# ESP32_wroom_C.net
KiCad netlist of a schematic drawn in EasyEDA Pro
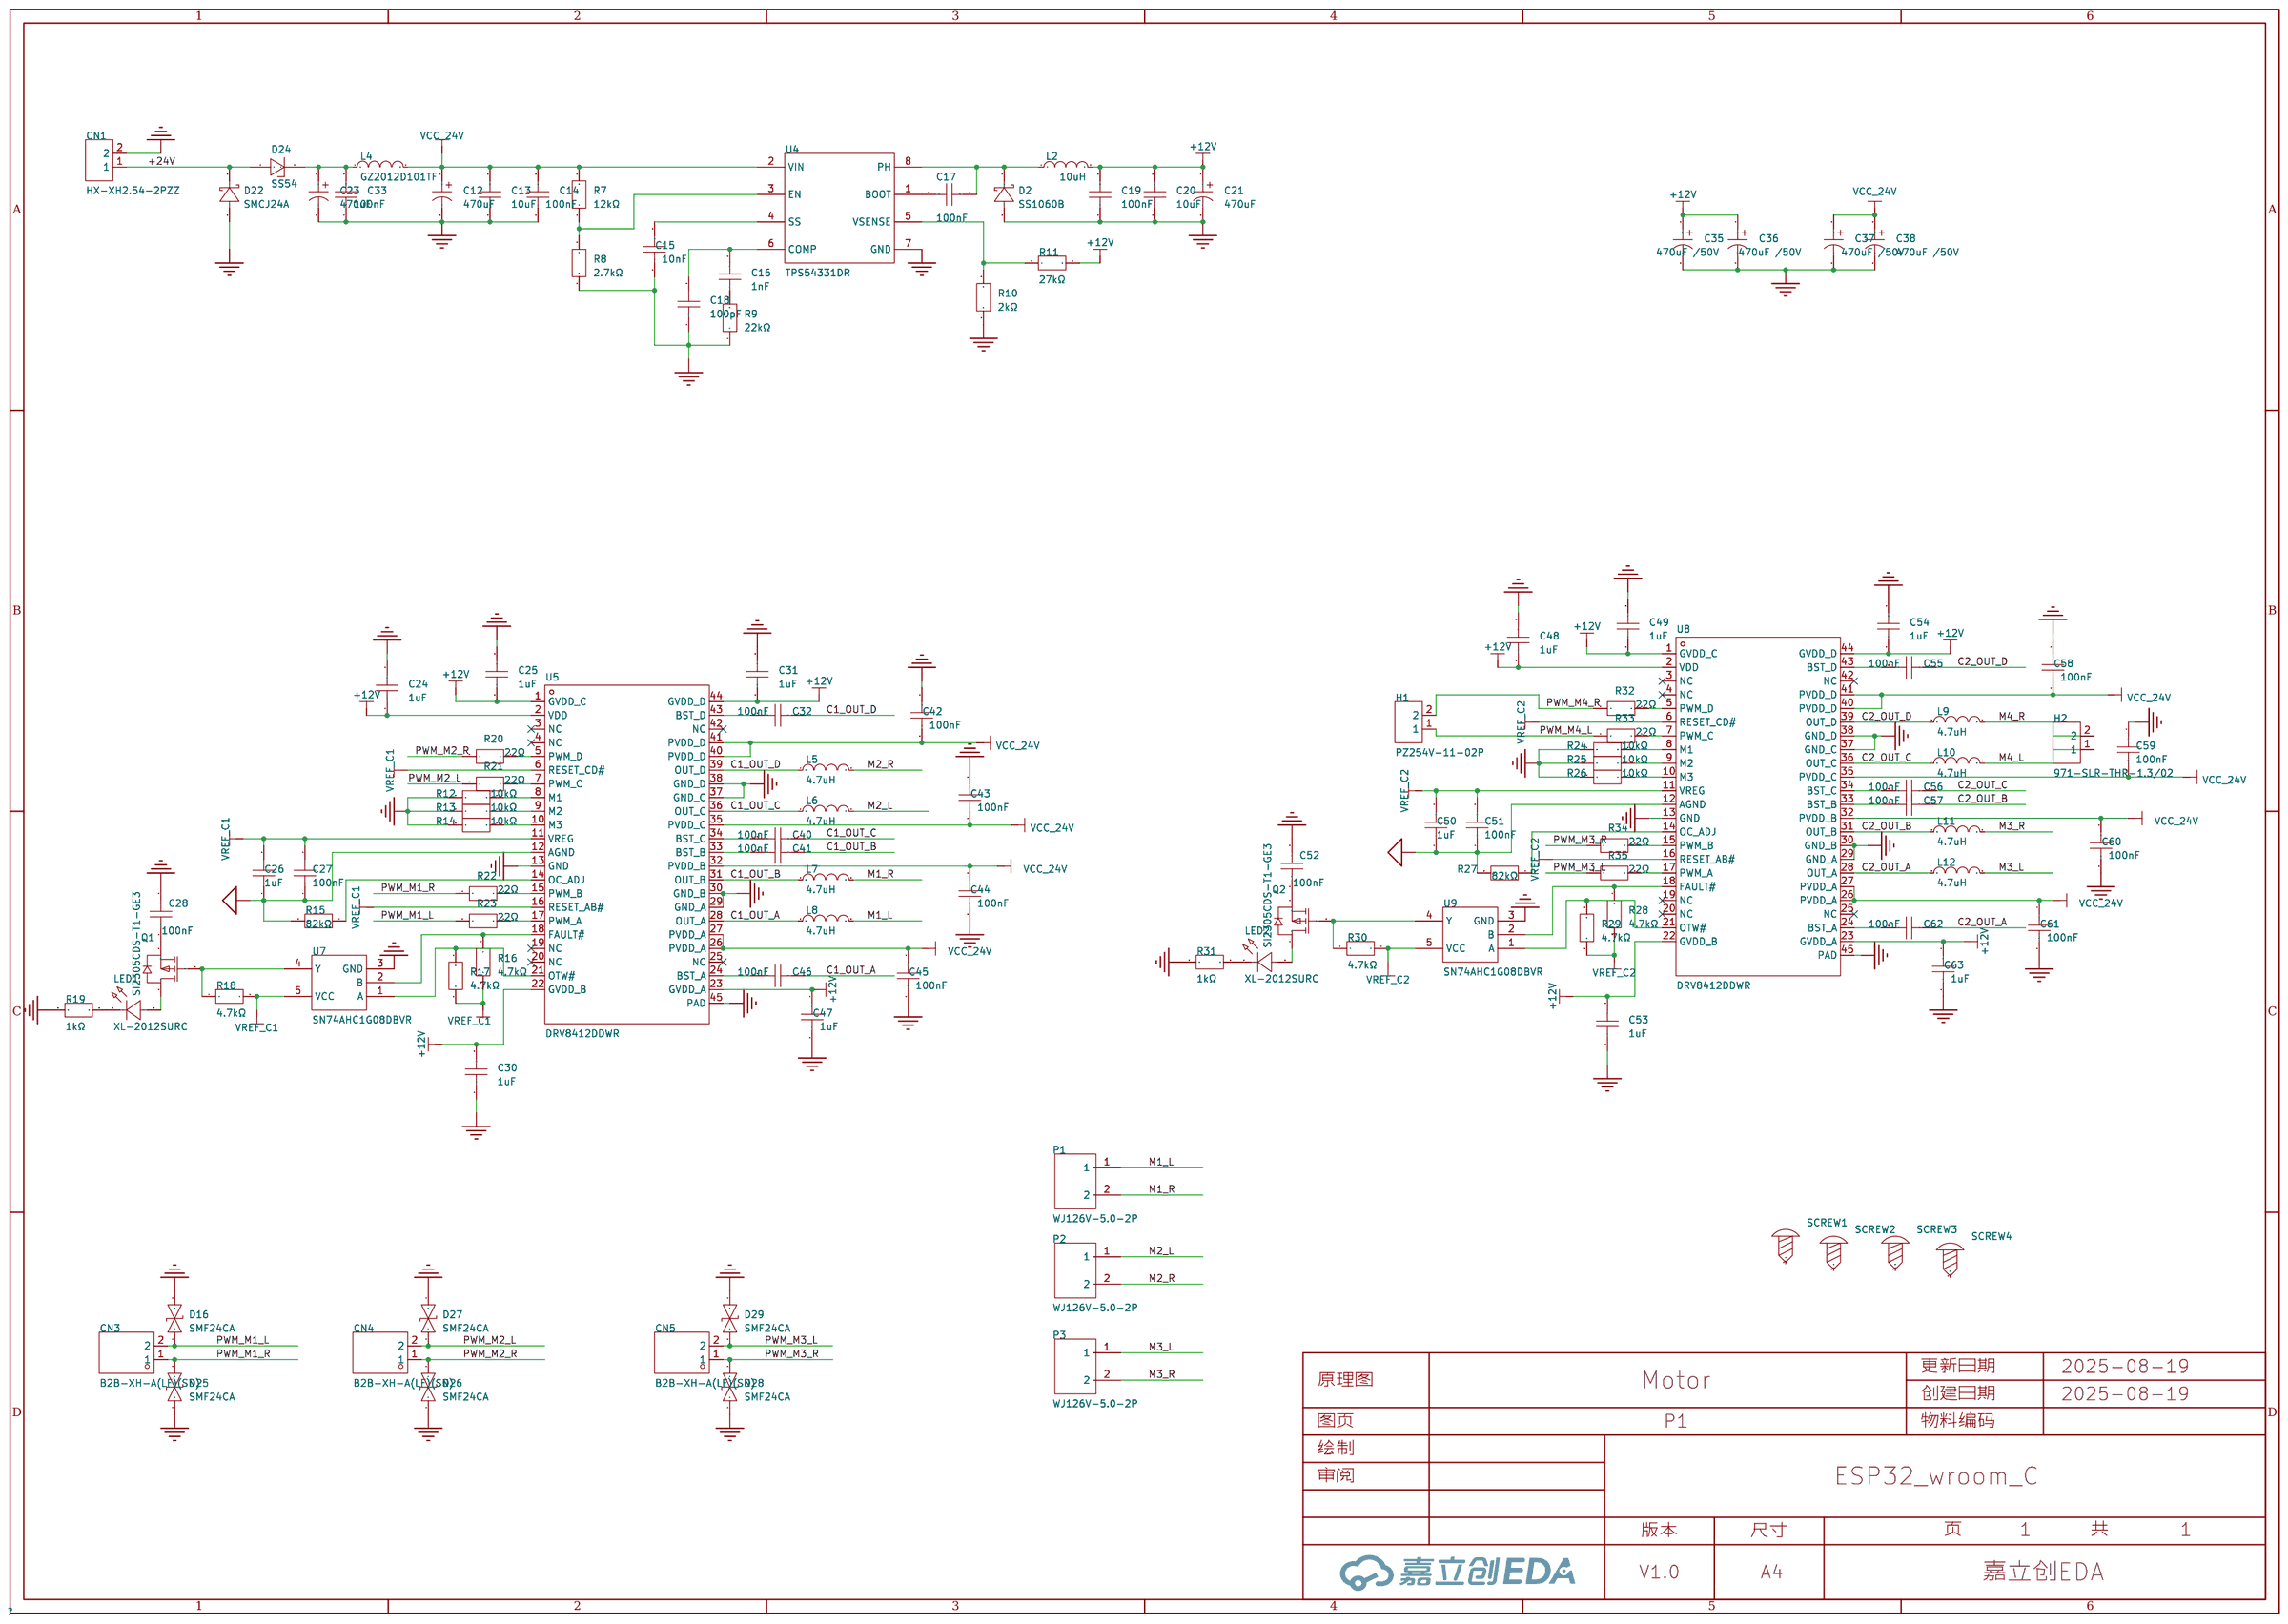
[diagram p0: schematic sheet]

(export (version "E")
  (design (tool "Eeschema 10.0.6"))
  (components
    (comp (ref "C12")
      (value "470uF")
      (footprint "easyedapro:CAP-TH_BD10.0-P5.00-D0.6-FD-A")
      (description "容值:470uF;精度:±20%;额定电压:50V;纹波电流:4.1A@100kHz;等效串联电阻(ESR):18mΩ@100kHz;类型:聚合物;")
      (fields (field (name "Manufacturer Part") "PA50V470M10x17") (field (name "Manufacturer") "捷而瑞"))
      (libsource (lib "easyedapro") (part "PA50V470M10X17"))
    )
    (comp (ref "C13")
      (value "10uF")
      (footprint "easyedapro:C0805")
      (description "容值:10uF;精度:±10%;额定电压:50V;材质(温度系数):X5R;")
      (fields
        (field (name "Manufacturer Part") "GRM21BR61H106KE43L")
        (field (name "Manufacturer") "muRata(村田)")
      )
      (libsource (lib "easyedapro") (part "GRM21BR61H106KE43L"))
    )
    (comp (ref "C14")
      (value "100nF")
      (footprint "easyedapro:C0603")
      (description "容值:100nF;精度:±10%;额定电压:50V;温度系数:X7R;")
      (fields
        (field (name "Manufacturer Part") "CGA0603X7R104K500JT")
        (field (name "Manufacturer") "HRE(芯声)")
      )
      (libsource (lib "easyedapro") (part "CGA0603X7R104K500JT"))
    )
    (comp (ref "C15")
      (value "10nF")
      (footprint "easyedapro:C0603")
      (description "容值:100nF;精度:±10%;额定电压:50V;温度系数:X7R;")
      (fields
        (field (name "Manufacturer Part") "CGA0603X7R104K500JT")
        (field (name "Manufacturer") "HRE(芯声)")
      )
      (libsource (lib "easyedapro") (part "CGA0603X7R104K500JT"))
    )
    (comp (ref "C16")
      (value "1nF")
      (footprint "easyedapro:C0603")
      (description "容值:100nF;精度:±10%;额定电压:50V;温度系数:X7R;")
      (fields
        (field (name "Manufacturer Part") "CGA0603X7R104K500JT")
        (field (name "Manufacturer") "HRE(芯声)")
      )
      (libsource (lib "easyedapro") (part "CGA0603X7R104K500JT"))
    )
    (comp (ref "C17")
      (value "100nF")
      (footprint "easyedapro:C0603")
      (description "容值:100nF;精度:±10%;额定电压:50V;温度系数:X7R;")
      (fields
        (field (name "Manufacturer Part") "CGA0603X7R104K500JT")
        (field (name "Manufacturer") "HRE(芯声)")
      )
      (libsource (lib "easyedapro") (part "CGA0603X7R104K500JT"))
    )
    (comp (ref "C18")
      (value "100pF")
      (footprint "easyedapro:C0603")
      (description "容值:100nF;精度:±10%;额定电压:50V;温度系数:X7R;")
      (fields
        (field (name "Manufacturer Part") "CGA0603X7R104K500JT")
        (field (name "Manufacturer") "HRE(芯声)")
      )
      (libsource (lib "easyedapro") (part "CGA0603X7R104K500JT"))
    )
    (comp (ref "C19")
      (value "100nF")
      (footprint "easyedapro:C0603")
      (description "容值:100nF;精度:±10%;额定电压:50V;温度系数:X7R;")
      (fields
        (field (name "Manufacturer Part") "CGA0603X7R104K500JT")
        (field (name "Manufacturer") "HRE(芯声)")
      )
      (libsource (lib "easyedapro") (part "CGA0603X7R104K500JT"))
    )
    (comp (ref "C20")
      (value "10uF")
      (footprint "easyedapro:C0805")
      (description "容值:10uF;精度:±10%;额定电压:50V;材质(温度系数):X5R;")
      (fields
        (field (name "Manufacturer Part") "GRM21BR61H106KE43L")
        (field (name "Manufacturer") "muRata(村田)")
      )
      (libsource (lib "easyedapro") (part "GRM21BR61H106KE43L"))
    )
    (comp (ref "C21")
      (value "470uF")
      (footprint "easyedapro:CAP-TH_BD10.0-P5.00-D0.6-FD-A")
      (description "容值:470uF;精度:±20%;额定电压:50V;纹波电流:4.1A@100kHz;等效串联电阻(ESR):18mΩ@100kHz;类型:聚合物;")
      (fields (field (name "Manufacturer Part") "PA50V470M10x17") (field (name "Manufacturer") "捷而瑞"))
      (libsource (lib "easyedapro") (part "PA50V470M10X17"))
    )
    (comp (ref "C23")
      (value "470uF")
      (footprint "easyedapro:CAP-TH_BD10.0-P5.00-D0.6-FD-A")
      (description "容值:470uF;精度:±20%;额定电压:50V;纹波电流:4.1A@100kHz;等效串联电阻(ESR):18mΩ@100kHz;类型:聚合物;")
      (fields (field (name "Manufacturer Part") "PA50V470M10x17") (field (name "Manufacturer") "捷而瑞"))
      (libsource (lib "easyedapro") (part "PA50V470M10X17"))
    )
    (comp (ref "C24")
      (value "1uF")
      (footprint "easyedapro:C0805")
      (description "容值:10uF;精度:±10%;额定电压:50V;材质(温度系数):X5R;")
      (fields
        (field (name "Manufacturer Part") "GRM21BR61H106KE43L")
        (field (name "Manufacturer") "muRata(村田)")
      )
      (libsource (lib "easyedapro") (part "GRM21BR61H106KE43L"))
    )
    (comp (ref "C25")
      (value "1uF")
      (footprint "easyedapro:C0805")
      (description "容值:10uF;精度:±10%;额定电压:50V;材质(温度系数):X5R;")
      (fields
        (field (name "Manufacturer Part") "GRM21BR61H106KE43L")
        (field (name "Manufacturer") "muRata(村田)")
      )
      (libsource (lib "easyedapro") (part "GRM21BR61H106KE43L"))
    )
    (comp (ref "C26")
      (value "1uF")
      (footprint "easyedapro:C0805")
      (description "容值:10uF;精度:±10%;额定电压:50V;材质(温度系数):X5R;")
      (fields
        (field (name "Manufacturer Part") "GRM21BR61H106KE43L")
        (field (name "Manufacturer") "muRata(村田)")
      )
      (libsource (lib "easyedapro") (part "GRM21BR61H106KE43L"))
    )
    (comp (ref "C27")
      (value "100nF")
      (footprint "easyedapro:C0805")
      (description "容值:10uF;精度:±10%;额定电压:50V;材质(温度系数):X5R;")
      (fields
        (field (name "Manufacturer Part") "GRM21BR61H106KE43L")
        (field (name "Manufacturer") "muRata(村田)")
      )
      (libsource (lib "easyedapro") (part "GRM21BR61H106KE43L"))
    )
    (comp (ref "C28")
      (value "100nF")
      (footprint "easyedapro:C0805")
      (description "容值:10uF;精度:±10%;额定电压:50V;材质(温度系数):X5R;")
      (fields
        (field (name "Manufacturer Part") "GRM21BR61H106KE43L")
        (field (name "Manufacturer") "muRata(村田)")
      )
      (libsource (lib "easyedapro") (part "GRM21BR61H106KE43L"))
    )
    (comp (ref "C30")
      (value "1uF")
      (footprint "easyedapro:C0805")
      (description "容值:10uF;精度:±10%;额定电压:50V;材质(温度系数):X5R;")
      (fields
        (field (name "Manufacturer Part") "GRM21BR61H106KE43L")
        (field (name "Manufacturer") "muRata(村田)")
      )
      (libsource (lib "easyedapro") (part "GRM21BR61H106KE43L"))
    )
    (comp (ref "C31")
      (value "1uF")
      (footprint "easyedapro:C0805")
      (description "容值:10uF;精度:±10%;额定电压:50V;材质(温度系数):X5R;")
      (fields
        (field (name "Manufacturer Part") "GRM21BR61H106KE43L")
        (field (name "Manufacturer") "muRata(村田)")
      )
      (libsource (lib "easyedapro") (part "GRM21BR61H106KE43L"))
    )
    (comp (ref "C32")
      (value "100nF")
      (footprint "easyedapro:C0805")
      (description "容值:10uF;精度:±10%;额定电压:50V;材质(温度系数):X5R;")
      (fields
        (field (name "Manufacturer Part") "GRM21BR61H106KE43L")
        (field (name "Manufacturer") "muRata(村田)")
      )
      (libsource (lib "easyedapro") (part "GRM21BR61H106KE43L"))
    )
    (comp (ref "C33")
      (value "100nF")
      (footprint "easyedapro:C0603")
      (description "容值:100nF;精度:±10%;额定电压:50V;温度系数:X7R;")
      (fields
        (field (name "Manufacturer Part") "CGA0603X7R104K500JT")
        (field (name "Manufacturer") "HRE(芯声)")
      )
      (libsource (lib "easyedapro") (part "CGA0603X7R104K500JT"))
    )
    (comp (ref "C35")
      (value "470uF /50V")
      (footprint "easyedapro:CAP-TH_BD10.0-P5.00-D0.6-FD-A")
      (description "容值:470uF;精度:±20%;额定电压:50V;纹波电流:4.1A@100kHz;等效串联电阻(ESR):18mΩ@100kHz;类型:聚合物;")
      (fields (field (name "Manufacturer Part") "PA50V470M10x17") (field (name "Manufacturer") "捷而瑞"))
      (libsource (lib "easyedapro") (part "PA50V470M10X17"))
    )
    (comp (ref "C36")
      (value "470uF /50V")
      (footprint "easyedapro:CAP-TH_BD10.0-P5.00-D0.6-FD-A")
      (description "容值:470uF;精度:±20%;额定电压:50V;纹波电流:4.1A@100kHz;等效串联电阻(ESR):18mΩ@100kHz;类型:聚合物;")
      (fields (field (name "Manufacturer Part") "PA50V470M10x17") (field (name "Manufacturer") "捷而瑞"))
      (libsource (lib "easyedapro") (part "PA50V470M10X17"))
    )
    (comp (ref "C37")
      (value "470uF /50V")
      (footprint "easyedapro:CAP-TH_BD10.0-P5.00-D0.6-FD-A")
      (description "容值:470uF;精度:±20%;额定电压:50V;纹波电流:4.1A@100kHz;等效串联电阻(ESR):18mΩ@100kHz;类型:聚合物;")
      (fields (field (name "Manufacturer Part") "PA50V470M10x17") (field (name "Manufacturer") "捷而瑞"))
      (libsource (lib "easyedapro") (part "PA50V470M10X17"))
    )
    (comp (ref "C38")
      (value "470uF /50V")
      (footprint "easyedapro:CAP-TH_BD10.0-P5.00-D0.6-FD-A")
      (description "容值:470uF;精度:±20%;额定电压:50V;纹波电流:4.1A@100kHz;等效串联电阻(ESR):18mΩ@100kHz;类型:聚合物;")
      (fields (field (name "Manufacturer Part") "PA50V470M10x17") (field (name "Manufacturer") "捷而瑞"))
      (libsource (lib "easyedapro") (part "PA50V470M10X17"))
    )
    (comp (ref "C40")
      (value "100nF")
      (footprint "easyedapro:C0805")
      (description "容值:10uF;精度:±10%;额定电压:50V;材质(温度系数):X5R;")
      (fields
        (field (name "Manufacturer Part") "GRM21BR61H106KE43L")
        (field (name "Manufacturer") "muRata(村田)")
      )
      (libsource (lib "easyedapro") (part "GRM21BR61H106KE43L"))
    )
    (comp (ref "C41")
      (value "100nF")
      (footprint "easyedapro:C0805")
      (description "容值:10uF;精度:±10%;额定电压:50V;材质(温度系数):X5R;")
      (fields
        (field (name "Manufacturer Part") "GRM21BR61H106KE43L")
        (field (name "Manufacturer") "muRata(村田)")
      )
      (libsource (lib "easyedapro") (part "GRM21BR61H106KE43L"))
    )
    (comp (ref "C42")
      (value "100nF")
      (footprint "easyedapro:C0805")
      (description "容值:10uF;精度:±10%;额定电压:50V;材质(温度系数):X5R;")
      (fields
        (field (name "Manufacturer Part") "GRM21BR61H106KE43L")
        (field (name "Manufacturer") "muRata(村田)")
      )
      (libsource (lib "easyedapro") (part "GRM21BR61H106KE43L"))
    )
    (comp (ref "C43")
      (value "100nF")
      (footprint "easyedapro:C0805")
      (description "容值:10uF;精度:±10%;额定电压:50V;材质(温度系数):X5R;")
      (fields
        (field (name "Manufacturer Part") "GRM21BR61H106KE43L")
        (field (name "Manufacturer") "muRata(村田)")
      )
      (libsource (lib "easyedapro") (part "GRM21BR61H106KE43L"))
    )
    (comp (ref "C44")
      (value "100nF")
      (footprint "easyedapro:C0805")
      (description "容值:10uF;精度:±10%;额定电压:50V;材质(温度系数):X5R;")
      (fields
        (field (name "Manufacturer Part") "GRM21BR61H106KE43L")
        (field (name "Manufacturer") "muRata(村田)")
      )
      (libsource (lib "easyedapro") (part "GRM21BR61H106KE43L"))
    )
    (comp (ref "C45")
      (value "100nF")
      (footprint "easyedapro:C0805")
      (description "容值:10uF;精度:±10%;额定电压:50V;材质(温度系数):X5R;")
      (fields
        (field (name "Manufacturer Part") "GRM21BR61H106KE43L")
        (field (name "Manufacturer") "muRata(村田)")
      )
      (libsource (lib "easyedapro") (part "GRM21BR61H106KE43L"))
    )
    (comp (ref "C46")
      (value "100nF")
      (footprint "easyedapro:C0805")
      (description "容值:10uF;精度:±10%;额定电压:50V;材质(温度系数):X5R;")
      (fields
        (field (name "Manufacturer Part") "GRM21BR61H106KE43L")
        (field (name "Manufacturer") "muRata(村田)")
      )
      (libsource (lib "easyedapro") (part "GRM21BR61H106KE43L"))
    )
    (comp (ref "C47")
      (value "1uF")
      (footprint "easyedapro:C0805")
      (description "容值:10uF;精度:±10%;额定电压:50V;材质(温度系数):X5R;")
      (fields
        (field (name "Manufacturer Part") "GRM21BR61H106KE43L")
        (field (name "Manufacturer") "muRata(村田)")
      )
      (libsource (lib "easyedapro") (part "GRM21BR61H106KE43L"))
    )
    (comp (ref "C48")
      (value "1uF")
      (footprint "easyedapro:C0805")
      (description "容值:10uF;精度:±10%;额定电压:50V;材质(温度系数):X5R;")
      (fields
        (field (name "Manufacturer Part") "GRM21BR61H106KE43L")
        (field (name "Manufacturer") "muRata(村田)")
      )
      (libsource (lib "easyedapro") (part "GRM21BR61H106KE43L"))
    )
    (comp (ref "C49")
      (value "1uF")
      (footprint "easyedapro:C0805")
      (description "容值:10uF;精度:±10%;额定电压:50V;材质(温度系数):X5R;")
      (fields
        (field (name "Manufacturer Part") "GRM21BR61H106KE43L")
        (field (name "Manufacturer") "muRata(村田)")
      )
      (libsource (lib "easyedapro") (part "GRM21BR61H106KE43L"))
    )
    (comp (ref "C50")
      (value "1uF")
      (footprint "easyedapro:C0805")
      (description "容值:10uF;精度:±10%;额定电压:50V;材质(温度系数):X5R;")
      (fields
        (field (name "Manufacturer Part") "GRM21BR61H106KE43L")
        (field (name "Manufacturer") "muRata(村田)")
      )
      (libsource (lib "easyedapro") (part "GRM21BR61H106KE43L"))
    )
    (comp (ref "C51")
      (value "100nF")
      (footprint "easyedapro:C0805")
      (description "容值:10uF;精度:±10%;额定电压:50V;材质(温度系数):X5R;")
      (fields
        (field (name "Manufacturer Part") "GRM21BR61H106KE43L")
        (field (name "Manufacturer") "muRata(村田)")
      )
      (libsource (lib "easyedapro") (part "GRM21BR61H106KE43L"))
    )
    (comp (ref "C52")
      (value "100nF")
      (footprint "easyedapro:C0805")
      (description "容值:10uF;精度:±10%;额定电压:50V;材质(温度系数):X5R;")
      (fields
        (field (name "Manufacturer Part") "GRM21BR61H106KE43L")
        (field (name "Manufacturer") "muRata(村田)")
      )
      (libsource (lib "easyedapro") (part "GRM21BR61H106KE43L"))
    )
    (comp (ref "C53")
      (value "1uF")
      (footprint "easyedapro:C0805")
      (description "容值:10uF;精度:±10%;额定电压:50V;材质(温度系数):X5R;")
      (fields
        (field (name "Manufacturer Part") "GRM21BR61H106KE43L")
        (field (name "Manufacturer") "muRata(村田)")
      )
      (libsource (lib "easyedapro") (part "GRM21BR61H106KE43L"))
    )
    (comp (ref "C54")
      (value "1uF")
      (footprint "easyedapro:C0805")
      (description "容值:10uF;精度:±10%;额定电压:50V;材质(温度系数):X5R;")
      (fields
        (field (name "Manufacturer Part") "GRM21BR61H106KE43L")
        (field (name "Manufacturer") "muRata(村田)")
      )
      (libsource (lib "easyedapro") (part "GRM21BR61H106KE43L"))
    )
    (comp (ref "C55")
      (value "100nF")
      (footprint "easyedapro:C0805")
      (description "容值:10uF;精度:±10%;额定电压:50V;材质(温度系数):X5R;")
      (fields
        (field (name "Manufacturer Part") "GRM21BR61H106KE43L")
        (field (name "Manufacturer") "muRata(村田)")
      )
      (libsource (lib "easyedapro") (part "GRM21BR61H106KE43L"))
    )
    (comp (ref "C56")
      (value "100nF")
      (footprint "easyedapro:C0805")
      (description "容值:10uF;精度:±10%;额定电压:50V;材质(温度系数):X5R;")
      (fields
        (field (name "Manufacturer Part") "GRM21BR61H106KE43L")
        (field (name "Manufacturer") "muRata(村田)")
      )
      (libsource (lib "easyedapro") (part "GRM21BR61H106KE43L"))
    )
    (comp (ref "C57")
      (value "100nF")
      (footprint "easyedapro:C0805")
      (description "容值:10uF;精度:±10%;额定电压:50V;材质(温度系数):X5R;")
      (fields
        (field (name "Manufacturer Part") "GRM21BR61H106KE43L")
        (field (name "Manufacturer") "muRata(村田)")
      )
      (libsource (lib "easyedapro") (part "GRM21BR61H106KE43L"))
    )
    (comp (ref "C58")
      (value "100nF")
      (footprint "easyedapro:C0805")
      (description "容值:10uF;精度:±10%;额定电压:50V;材质(温度系数):X5R;")
      (fields
        (field (name "Manufacturer Part") "GRM21BR61H106KE43L")
        (field (name "Manufacturer") "muRata(村田)")
      )
      (libsource (lib "easyedapro") (part "GRM21BR61H106KE43L"))
    )
    (comp (ref "C59")
      (value "100nF")
      (footprint "easyedapro:C0805")
      (description "容值:10uF;精度:±10%;额定电压:50V;材质(温度系数):X5R;")
      (fields
        (field (name "Manufacturer Part") "GRM21BR61H106KE43L")
        (field (name "Manufacturer") "muRata(村田)")
      )
      (libsource (lib "easyedapro") (part "GRM21BR61H106KE43L"))
    )
    (comp (ref "C60")
      (value "100nF")
      (footprint "easyedapro:C0805")
      (description "容值:10uF;精度:±10%;额定电压:50V;材质(温度系数):X5R;")
      (fields
        (field (name "Manufacturer Part") "GRM21BR61H106KE43L")
        (field (name "Manufacturer") "muRata(村田)")
      )
      (libsource (lib "easyedapro") (part "GRM21BR61H106KE43L"))
    )
    (comp (ref "C61")
      (value "100nF")
      (footprint "easyedapro:C0805")
      (description "容值:10uF;精度:±10%;额定电压:50V;材质(温度系数):X5R;")
      (fields
        (field (name "Manufacturer Part") "GRM21BR61H106KE43L")
        (field (name "Manufacturer") "muRata(村田)")
      )
      (libsource (lib "easyedapro") (part "GRM21BR61H106KE43L"))
    )
    (comp (ref "C62")
      (value "100nF")
      (footprint "easyedapro:C0805")
      (description "容值:10uF;精度:±10%;额定电压:50V;材质(温度系数):X5R;")
      (fields
        (field (name "Manufacturer Part") "GRM21BR61H106KE43L")
        (field (name "Manufacturer") "muRata(村田)")
      )
      (libsource (lib "easyedapro") (part "GRM21BR61H106KE43L"))
    )
    (comp (ref "C63")
      (value "1uF")
      (footprint "easyedapro:C0805")
      (description "容值:10uF;精度:±10%;额定电压:50V;材质(温度系数):X5R;")
      (fields
        (field (name "Manufacturer Part") "GRM21BR61H106KE43L")
        (field (name "Manufacturer") "muRata(村田)")
      )
      (libsource (lib "easyedapro") (part "GRM21BR61H106KE43L"))
    )
    (comp (ref "CN1")
      (value "HX-XH2.54-2PZZ")
      (footprint "easyedapro:CONN-TH_2P-P2.50_HX-2.54MM-2P-ZZ-MS")
      (fields (field (name "Manufacturer") "hanxia(韩下)"))
      (libsource (lib "easyedapro") (part "HX-XH2.54-2PZZ"))
    )
    (comp (ref "CN3")
      (value "B2B-XH-A(LF)(SN)")
      (footprint "easyedapro:CONN-TH_B2B-XH-A-LF-SN")
      (fields (field (name "Manufacturer") "JST"))
      (libsource (lib "easyedapro") (part "B2B-XH-A (LF)(SN)"))
    )
    (comp (ref "CN4")
      (value "B2B-XH-A(LF)(SN)")
      (footprint "easyedapro:CONN-TH_B2B-XH-A-LF-SN")
      (fields (field (name "Manufacturer") "JST"))
      (libsource (lib "easyedapro") (part "B2B-XH-A (LF)(SN)"))
    )
    (comp (ref "CN5")
      (value "B2B-XH-A(LF)(SN)")
      (footprint "easyedapro:CONN-TH_B2B-XH-A-LF-SN")
      (fields (field (name "Manufacturer") "JST"))
      (libsource (lib "easyedapro") (part "B2B-XH-A (LF)(SN)"))
    )
    (comp (ref "D2")
      (value "SS1060B")
      (footprint "easyedapro:SMB_L4.3-W3.6-LS5.3-RD")
      (description "正向压降(Vf):700mV@10A;直流反向耐压(Vr):60V;整流电流:10A;")
      (fields (field (name "Manufacturer") "Slkor(萨科微)"))
      (libsource (lib "easyedapro") (part "SS1060B_C18208635"))
    )
    (comp (ref "D16")
      (value "SMF24CA")
      (footprint "easyedapro:SOD-123FL_L2.7-W1.8-LS3.8-BI")
      (fields (field (name "Manufacturer") "宏迦橙"))
      (libsource (lib "easyedapro") (part "SMF24CA_C19077515"))
    )
    (comp (ref "D22")
      (value "SMCJ24A")
      (footprint "easyedapro:SMC_L6.9-W5.9-LS7.9-RD")
      (fields (field (name "Manufacturer") "宏嘉诚"))
      (libsource (lib "easyedapro") (part "SMCJ24A_C19077604"))
    )
    (comp (ref "D24")
      (value "SS54")
      (footprint "easyedapro:SMA_L4.3-W2.6-LS5.0-FD")
      (description "二极管配置:独立式;正向压降(Vf):550mV@5.0A;直流反向耐压(Vr):40V;整流电流:5A;")
      (fields (field (name "Manufacturer") "宏嘉诚"))
      (libsource (lib "easyedapro") (part "SS54_C7420369"))
    )
    (comp (ref "D25")
      (value "SMF24CA")
      (footprint "easyedapro:SOD-123FL_L2.7-W1.8-LS3.8-BI")
      (fields (field (name "Manufacturer") "宏迦橙"))
      (libsource (lib "easyedapro") (part "SMF24CA_C19077515"))
    )
    (comp (ref "D26")
      (value "SMF24CA")
      (footprint "easyedapro:SOD-123FL_L2.7-W1.8-LS3.8-BI")
      (fields (field (name "Manufacturer") "宏迦橙"))
      (libsource (lib "easyedapro") (part "SMF24CA_C19077515"))
    )
    (comp (ref "D27")
      (value "SMF24CA")
      (footprint "easyedapro:SOD-123FL_L2.7-W1.8-LS3.8-BI")
      (fields (field (name "Manufacturer") "宏迦橙"))
      (libsource (lib "easyedapro") (part "SMF24CA_C19077515"))
    )
    (comp (ref "D28")
      (value "SMF24CA")
      (footprint "easyedapro:SOD-123FL_L2.7-W1.8-LS3.8-BI")
      (fields (field (name "Manufacturer") "宏迦橙"))
      (libsource (lib "easyedapro") (part "SMF24CA_C19077515"))
    )
    (comp (ref "D29")
      (value "SMF24CA")
      (footprint "easyedapro:SOD-123FL_L2.7-W1.8-LS3.8-BI")
      (fields (field (name "Manufacturer") "宏迦橙"))
      (libsource (lib "easyedapro") (part "SMF24CA_C19077515"))
    )
    (comp (ref "H1")
      (value "PZ254V-11-02P")
      (footprint "easyedapro:HDR-TH_2P-P2.54-V-M")
      (fields (field (name "Manufacturer") "XFCN(兴飞)"))
      (libsource (lib "easyedapro") (part "PZ254V-11-02P"))
    )
    (comp (ref "H2")
      (value "971-SLR-THR-1.3/02")
      (footprint "easyedapro:HDR-TH_2P-P5.00-V-M")
      (fields (field (name "Manufacturer") "WECO(威克德诺)"))
      (libsource (lib "easyedapro") (part "971-SLR-THR-1.3/02"))
    )
    (comp (ref "L2")
      (value "10uH")
      (footprint "easyedapro:IND-SMD_L7.1-W6.6")
      (description "电感值:10uH;精度:±20%;饱和电流(Isat):4.5A;类型:一体成型电感;")
      (fields (field (name "Manufacturer Part") "D0630HP-100MT") (field (name "Manufacturer") "DEYAN(德砚电子)"))
      (libsource (lib "easyedapro") (part "D0630HP-100MT"))
    )
    (comp (ref "L4")
      (value "GZ2012D101TF")
      (footprint "easyedapro:L0805")
      (description "阻抗@频率:100Ω@100MHz;误差:±25%;直流电阻(DCR):150mΩ;")
      (fields (field (name "Manufacturer") "Sunlord(顺络)"))
      (libsource (lib "easyedapro") (part "GZ2012D101TF"))
    )
    (comp (ref "L5")
      (value "4.7uH")
      (footprint "easyedapro:IND-SMD_L4.0-W4.0")
      (description "电感值:4.7uH;精度:±20%;额定电流:2A;饱和电流(Isat):3.2A;类型:-;")
      (fields (field (name "Manufacturer Part") "SWPA4030S4R7MT") (field (name "Manufacturer") "Sunlord(顺络)"))
      (libsource (lib "easyedapro") (part "SWPA4030S4R7MT"))
    )
    (comp (ref "L6")
      (value "4.7uH")
      (footprint "easyedapro:IND-SMD_L4.0-W4.0")
      (description "电感值:4.7uH;精度:±20%;额定电流:2A;饱和电流(Isat):3.2A;类型:-;")
      (fields (field (name "Manufacturer Part") "SWPA4030S4R7MT") (field (name "Manufacturer") "Sunlord(顺络)"))
      (libsource (lib "easyedapro") (part "SWPA4030S4R7MT"))
    )
    (comp (ref "L7")
      (value "4.7uH")
      (footprint "easyedapro:IND-SMD_L4.0-W4.0")
      (description "电感值:4.7uH;精度:±20%;额定电流:2A;饱和电流(Isat):3.2A;类型:-;")
      (fields (field (name "Manufacturer Part") "SWPA4030S4R7MT") (field (name "Manufacturer") "Sunlord(顺络)"))
      (libsource (lib "easyedapro") (part "SWPA4030S4R7MT"))
    )
    (comp (ref "L8")
      (value "4.7uH")
      (footprint "easyedapro:IND-SMD_L4.0-W4.0")
      (description "电感值:4.7uH;精度:±20%;额定电流:2A;饱和电流(Isat):3.2A;类型:-;")
      (fields (field (name "Manufacturer Part") "SWPA4030S4R7MT") (field (name "Manufacturer") "Sunlord(顺络)"))
      (libsource (lib "easyedapro") (part "SWPA4030S4R7MT"))
    )
    (comp (ref "L9")
      (value "4.7uH")
      (footprint "easyedapro:IND-SMD_L4.0-W4.0")
      (description "电感值:4.7uH;精度:±20%;额定电流:2A;饱和电流(Isat):3.2A;类型:-;")
      (fields (field (name "Manufacturer Part") "SWPA4030S4R7MT") (field (name "Manufacturer") "Sunlord(顺络)"))
      (libsource (lib "easyedapro") (part "SWPA4030S4R7MT"))
    )
    (comp (ref "L10")
      (value "4.7uH")
      (footprint "easyedapro:IND-SMD_L4.0-W4.0")
      (description "电感值:4.7uH;精度:±20%;额定电流:2A;饱和电流(Isat):3.2A;类型:-;")
      (fields (field (name "Manufacturer Part") "SWPA4030S4R7MT") (field (name "Manufacturer") "Sunlord(顺络)"))
      (libsource (lib "easyedapro") (part "SWPA4030S4R7MT"))
    )
    (comp (ref "L11")
      (value "4.7uH")
      (footprint "easyedapro:IND-SMD_L4.0-W4.0")
      (description "电感值:4.7uH;精度:±20%;额定电流:2A;饱和电流(Isat):3.2A;类型:-;")
      (fields (field (name "Manufacturer Part") "SWPA4030S4R7MT") (field (name "Manufacturer") "Sunlord(顺络)"))
      (libsource (lib "easyedapro") (part "SWPA4030S4R7MT"))
    )
    (comp (ref "L12")
      (value "4.7uH")
      (footprint "easyedapro:IND-SMD_L4.0-W4.0")
      (description "电感值:4.7uH;精度:±20%;额定电流:2A;饱和电流(Isat):3.2A;类型:-;")
      (fields (field (name "Manufacturer Part") "SWPA4030S4R7MT") (field (name "Manufacturer") "Sunlord(顺络)"))
      (libsource (lib "easyedapro") (part "SWPA4030S4R7MT"))
    )
    (comp (ref "LED1")
      (value "XL-2012SURC")
      (footprint "easyedapro:LED0805-RD_RED")
      (description "发光颜色:红色;功率:55mW;正向电流:25mA;主波长:617nm~621nm;透镜颜色:无色透明透镜;色温:-;发光角度:120°;载带方式:正贴;工作温度:-30°C~+85°C;")
      (fields (field (name "Manufacturer") "XINGLIGHT(成兴光)"))
      (libsource (lib "easyedapro") (part "XL-2012SURC"))
    )
    (comp (ref "LED2")
      (value "XL-2012SURC")
      (footprint "easyedapro:LED0805-RD_RED")
      (description "发光颜色:红色;功率:55mW;正向电流:25mA;主波长:617nm~621nm;透镜颜色:无色透明透镜;色温:-;发光角度:120°;载带方式:正贴;工作温度:-30°C~+85°C;")
      (fields (field (name "Manufacturer") "XINGLIGHT(成兴光)"))
      (libsource (lib "easyedapro") (part "XL-2012SURC"))
    )
    (comp (ref "P1")
      (value "WJ126V-5.0-2P")
      (footprint "easyedapro:CONN-TH_WJ126V-5.0-2P")
      (fields (field (name "Manufacturer") "KANGNEX(康奈克斯电气)"))
      (libsource (lib "easyedapro") (part "WJ126V-5.0-2P"))
    )
    (comp (ref "P2")
      (value "WJ126V-5.0-2P")
      (footprint "easyedapro:CONN-TH_WJ126V-5.0-2P")
      (fields (field (name "Manufacturer") "KANGNEX(康奈克斯电气)"))
      (libsource (lib "easyedapro") (part "WJ126V-5.0-2P"))
    )
    (comp (ref "P3")
      (value "WJ126V-5.0-2P")
      (footprint "easyedapro:CONN-TH_WJ126V-5.0-2P")
      (fields (field (name "Manufacturer") "KANGNEX(康奈克斯电气)"))
      (libsource (lib "easyedapro") (part "WJ126V-5.0-2P"))
    )
    (comp (ref "Q1")
      (value "SI2305CDS-T1-GE3")
      (footprint "easyedapro:SOT-23-3_L2.9-W1.3-P1.90-LS2.4-BR")
      (fields (field (name "Manufacturer") "VISHAY(威世)"))
      (libsource (lib "easyedapro") (part "SI2305CDS-T1-GE3"))
    )
    (comp (ref "Q2")
      (value "SI2305CDS-T1-GE3")
      (footprint "easyedapro:SOT-23-3_L2.9-W1.3-P1.90-LS2.4-BR")
      (fields (field (name "Manufacturer") "VISHAY(威世)"))
      (libsource (lib "easyedapro") (part "SI2305CDS-T1-GE3"))
    )
    (comp (ref "R7")
      (value "12kΩ")
      (footprint "easyedapro:R0603")
      (description "电阻类型:厚膜电阻;阻值:12kΩ;精度:±5%;功率:100mW;工作电压:75V;温度系数:±100ppm/°C;")
      (fields (field (name "Manufacturer Part") "FRC0603J123 TS") (field (name "Manufacturer") "FOJAN(富捷)"))
      (libsource (lib "easyedapro") (part "FRC0603J123 TS"))
    )
    (comp (ref "R8")
      (value "2.7kΩ")
      (footprint "easyedapro:R0603")
      (description "电阻类型:厚膜电阻;阻值:12kΩ;精度:±5%;功率:100mW;工作电压:75V;温度系数:±100ppm/°C;")
      (fields (field (name "Manufacturer Part") "FRC0603J123 TS") (field (name "Manufacturer") "FOJAN(富捷)"))
      (libsource (lib "easyedapro") (part "FRC0603J123 TS"))
    )
    (comp (ref "R9")
      (value "22kΩ")
      (footprint "easyedapro:R0603")
      (description "电阻类型:厚膜电阻;阻值:12kΩ;精度:±5%;功率:100mW;工作电压:75V;温度系数:±100ppm/°C;")
      (fields (field (name "Manufacturer Part") "FRC0603J123 TS") (field (name "Manufacturer") "FOJAN(富捷)"))
      (libsource (lib "easyedapro") (part "FRC0603J123 TS"))
    )
    (comp (ref "R10")
      (value "2kΩ")
      (footprint "easyedapro:R0603")
      (description "电阻类型:厚膜电阻;阻值:12kΩ;精度:±5%;功率:100mW;工作电压:75V;温度系数:±100ppm/°C;")
      (fields (field (name "Manufacturer Part") "FRC0603J123 TS") (field (name "Manufacturer") "FOJAN(富捷)"))
      (libsource (lib "easyedapro") (part "FRC0603J123 TS"))
    )
    (comp (ref "R11")
      (value "27kΩ")
      (footprint "easyedapro:R0603")
      (description "电阻类型:厚膜电阻;阻值:12kΩ;精度:±5%;功率:100mW;工作电压:75V;温度系数:±100ppm/°C;")
      (fields (field (name "Manufacturer Part") "FRC0603J123 TS") (field (name "Manufacturer") "FOJAN(富捷)"))
      (libsource (lib "easyedapro") (part "FRC0603J123 TS"))
    )
    (comp (ref "R12")
      (value "10kΩ")
      (footprint "easyedapro:R0603")
      (description "电阻类型:厚膜电阻;阻值:12kΩ;精度:±5%;功率:100mW;工作电压:75V;温度系数:±100ppm/°C;")
      (fields (field (name "Manufacturer Part") "FRC0603J123 TS") (field (name "Manufacturer") "FOJAN(富捷)"))
      (libsource (lib "easyedapro") (part "FRC0603J123 TS"))
    )
    (comp (ref "R13")
      (value "10kΩ")
      (footprint "easyedapro:R0603")
      (description "电阻类型:厚膜电阻;阻值:12kΩ;精度:±5%;功率:100mW;工作电压:75V;温度系数:±100ppm/°C;")
      (fields (field (name "Manufacturer Part") "FRC0603J123 TS") (field (name "Manufacturer") "FOJAN(富捷)"))
      (libsource (lib "easyedapro") (part "FRC0603J123 TS"))
    )
    (comp (ref "R14")
      (value "10kΩ")
      (footprint "easyedapro:R0603")
      (description "电阻类型:厚膜电阻;阻值:12kΩ;精度:±5%;功率:100mW;工作电压:75V;温度系数:±100ppm/°C;")
      (fields (field (name "Manufacturer Part") "FRC0603J123 TS") (field (name "Manufacturer") "FOJAN(富捷)"))
      (libsource (lib "easyedapro") (part "FRC0603J123 TS"))
    )
    (comp (ref "R15")
      (value "82kΩ")
      (footprint "easyedapro:R0603")
      (description "电阻类型:厚膜电阻;阻值:12kΩ;精度:±5%;功率:100mW;工作电压:75V;温度系数:±100ppm/°C;")
      (fields (field (name "Manufacturer Part") "FRC0603J123 TS") (field (name "Manufacturer") "FOJAN(富捷)"))
      (libsource (lib "easyedapro") (part "FRC0603J123 TS"))
    )
    (comp (ref "R16")
      (value "4.7kΩ")
      (footprint "easyedapro:R0603")
      (description "电阻类型:厚膜电阻;阻值:12kΩ;精度:±5%;功率:100mW;工作电压:75V;温度系数:±100ppm/°C;")
      (fields (field (name "Manufacturer Part") "FRC0603J123 TS") (field (name "Manufacturer") "FOJAN(富捷)"))
      (libsource (lib "easyedapro") (part "FRC0603J123 TS"))
    )
    (comp (ref "R17")
      (value "4.7kΩ")
      (footprint "easyedapro:R0603")
      (description "电阻类型:厚膜电阻;阻值:12kΩ;精度:±5%;功率:100mW;工作电压:75V;温度系数:±100ppm/°C;")
      (fields (field (name "Manufacturer Part") "FRC0603J123 TS") (field (name "Manufacturer") "FOJAN(富捷)"))
      (libsource (lib "easyedapro") (part "FRC0603J123 TS"))
    )
    (comp (ref "R18")
      (value "4.7kΩ")
      (footprint "easyedapro:R0603")
      (description "电阻类型:厚膜电阻;阻值:12kΩ;精度:±5%;功率:100mW;工作电压:75V;温度系数:±100ppm/°C;")
      (fields (field (name "Manufacturer Part") "FRC0603J123 TS") (field (name "Manufacturer") "FOJAN(富捷)"))
      (libsource (lib "easyedapro") (part "FRC0603J123 TS"))
    )
    (comp (ref "R19")
      (value "1kΩ")
      (footprint "easyedapro:R0603")
      (description "电阻类型:厚膜电阻;阻值:12kΩ;精度:±5%;功率:100mW;工作电压:75V;温度系数:±100ppm/°C;")
      (fields (field (name "Manufacturer Part") "FRC0603J123 TS") (field (name "Manufacturer") "FOJAN(富捷)"))
      (libsource (lib "easyedapro") (part "FRC0603J123 TS"))
    )
    (comp (ref "R20")
      (value "22Ω")
      (footprint "easyedapro:R0603")
      (description "电阻类型:厚膜电阻;阻值:12kΩ;精度:±5%;功率:100mW;工作电压:75V;温度系数:±100ppm/°C;")
      (fields (field (name "Manufacturer Part") "FRC0603J123 TS") (field (name "Manufacturer") "FOJAN(富捷)"))
      (libsource (lib "easyedapro") (part "FRC0603J123 TS"))
    )
    (comp (ref "R21")
      (value "22Ω")
      (footprint "easyedapro:R0603")
      (description "电阻类型:厚膜电阻;阻值:12kΩ;精度:±5%;功率:100mW;工作电压:75V;温度系数:±100ppm/°C;")
      (fields (field (name "Manufacturer Part") "FRC0603J123 TS") (field (name "Manufacturer") "FOJAN(富捷)"))
      (libsource (lib "easyedapro") (part "FRC0603J123 TS"))
    )
    (comp (ref "R22")
      (value "22Ω")
      (footprint "easyedapro:R0603")
      (description "电阻类型:厚膜电阻;阻值:12kΩ;精度:±5%;功率:100mW;工作电压:75V;温度系数:±100ppm/°C;")
      (fields (field (name "Manufacturer Part") "FRC0603J123 TS") (field (name "Manufacturer") "FOJAN(富捷)"))
      (libsource (lib "easyedapro") (part "FRC0603J123 TS"))
    )
    (comp (ref "R23")
      (value "22Ω")
      (footprint "easyedapro:R0603")
      (description "电阻类型:厚膜电阻;阻值:12kΩ;精度:±5%;功率:100mW;工作电压:75V;温度系数:±100ppm/°C;")
      (fields (field (name "Manufacturer Part") "FRC0603J123 TS") (field (name "Manufacturer") "FOJAN(富捷)"))
      (libsource (lib "easyedapro") (part "FRC0603J123 TS"))
    )
    (comp (ref "R24")
      (value "10kΩ")
      (footprint "easyedapro:R0603")
      (description "电阻类型:厚膜电阻;阻值:12kΩ;精度:±5%;功率:100mW;工作电压:75V;温度系数:±100ppm/°C;")
      (fields (field (name "Manufacturer Part") "FRC0603J123 TS") (field (name "Manufacturer") "FOJAN(富捷)"))
      (libsource (lib "easyedapro") (part "FRC0603J123 TS"))
    )
    (comp (ref "R25")
      (value "10kΩ")
      (footprint "easyedapro:R0603")
      (description "电阻类型:厚膜电阻;阻值:12kΩ;精度:±5%;功率:100mW;工作电压:75V;温度系数:±100ppm/°C;")
      (fields (field (name "Manufacturer Part") "FRC0603J123 TS") (field (name "Manufacturer") "FOJAN(富捷)"))
      (libsource (lib "easyedapro") (part "FRC0603J123 TS"))
    )
    (comp (ref "R26")
      (value "10kΩ")
      (footprint "easyedapro:R0603")
      (description "电阻类型:厚膜电阻;阻值:12kΩ;精度:±5%;功率:100mW;工作电压:75V;温度系数:±100ppm/°C;")
      (fields (field (name "Manufacturer Part") "FRC0603J123 TS") (field (name "Manufacturer") "FOJAN(富捷)"))
      (libsource (lib "easyedapro") (part "FRC0603J123 TS"))
    )
    (comp (ref "R27")
      (value "82kΩ")
      (footprint "easyedapro:R0603")
      (description "电阻类型:厚膜电阻;阻值:12kΩ;精度:±5%;功率:100mW;工作电压:75V;温度系数:±100ppm/°C;")
      (fields (field (name "Manufacturer Part") "FRC0603J123 TS") (field (name "Manufacturer") "FOJAN(富捷)"))
      (libsource (lib "easyedapro") (part "FRC0603J123 TS"))
    )
    (comp (ref "R28")
      (value "4.7kΩ")
      (footprint "easyedapro:R0603")
      (description "电阻类型:厚膜电阻;阻值:12kΩ;精度:±5%;功率:100mW;工作电压:75V;温度系数:±100ppm/°C;")
      (fields (field (name "Manufacturer Part") "FRC0603J123 TS") (field (name "Manufacturer") "FOJAN(富捷)"))
      (libsource (lib "easyedapro") (part "FRC0603J123 TS"))
    )
    (comp (ref "R29")
      (value "4.7kΩ")
      (footprint "easyedapro:R0603")
      (description "电阻类型:厚膜电阻;阻值:12kΩ;精度:±5%;功率:100mW;工作电压:75V;温度系数:±100ppm/°C;")
      (fields (field (name "Manufacturer Part") "FRC0603J123 TS") (field (name "Manufacturer") "FOJAN(富捷)"))
      (libsource (lib "easyedapro") (part "FRC0603J123 TS"))
    )
    (comp (ref "R30")
      (value "4.7kΩ")
      (footprint "easyedapro:R0603")
      (description "电阻类型:厚膜电阻;阻值:12kΩ;精度:±5%;功率:100mW;工作电压:75V;温度系数:±100ppm/°C;")
      (fields (field (name "Manufacturer Part") "FRC0603J123 TS") (field (name "Manufacturer") "FOJAN(富捷)"))
      (libsource (lib "easyedapro") (part "FRC0603J123 TS"))
    )
    (comp (ref "R31")
      (value "1kΩ")
      (footprint "easyedapro:R0603")
      (description "电阻类型:厚膜电阻;阻值:12kΩ;精度:±5%;功率:100mW;工作电压:75V;温度系数:±100ppm/°C;")
      (fields (field (name "Manufacturer Part") "FRC0603J123 TS") (field (name "Manufacturer") "FOJAN(富捷)"))
      (libsource (lib "easyedapro") (part "FRC0603J123 TS"))
    )
    (comp (ref "R32")
      (value "22Ω")
      (footprint "easyedapro:R0603")
      (description "电阻类型:厚膜电阻;阻值:12kΩ;精度:±5%;功率:100mW;工作电压:75V;温度系数:±100ppm/°C;")
      (fields (field (name "Manufacturer Part") "FRC0603J123 TS") (field (name "Manufacturer") "FOJAN(富捷)"))
      (libsource (lib "easyedapro") (part "FRC0603J123 TS"))
    )
    (comp (ref "R33")
      (value "22Ω")
      (footprint "easyedapro:R0603")
      (description "电阻类型:厚膜电阻;阻值:12kΩ;精度:±5%;功率:100mW;工作电压:75V;温度系数:±100ppm/°C;")
      (fields (field (name "Manufacturer Part") "FRC0603J123 TS") (field (name "Manufacturer") "FOJAN(富捷)"))
      (libsource (lib "easyedapro") (part "FRC0603J123 TS"))
    )
    (comp (ref "R34")
      (value "22Ω")
      (footprint "easyedapro:R0603")
      (description "电阻类型:厚膜电阻;阻值:12kΩ;精度:±5%;功率:100mW;工作电压:75V;温度系数:±100ppm/°C;")
      (fields (field (name "Manufacturer Part") "FRC0603J123 TS") (field (name "Manufacturer") "FOJAN(富捷)"))
      (libsource (lib "easyedapro") (part "FRC0603J123 TS"))
    )
    (comp (ref "R35")
      (value "22Ω")
      (footprint "easyedapro:R0603")
      (description "电阻类型:厚膜电阻;阻值:12kΩ;精度:±5%;功率:100mW;工作电压:75V;温度系数:±100ppm/°C;")
      (fields (field (name "Manufacturer Part") "FRC0603J123 TS") (field (name "Manufacturer") "FOJAN(富捷)"))
      (libsource (lib "easyedapro") (part "FRC0603J123 TS"))
    )
    (comp (ref "SCREW1")
      (value "~")
      (footprint "easyedapro:M3螺丝")
      (libsource (lib "easyedapro") (part "螺丝孔"))
    )
    (comp (ref "SCREW2")
      (value "~")
      (footprint "easyedapro:M3螺丝")
      (libsource (lib "easyedapro") (part "螺丝孔"))
    )
    (comp (ref "SCREW3")
      (value "~")
      (footprint "easyedapro:M3螺丝")
      (libsource (lib "easyedapro") (part "螺丝孔"))
    )
    (comp (ref "SCREW4")
      (value "~")
      (footprint "easyedapro:M3螺丝")
      (libsource (lib "easyedapro") (part "螺丝孔"))
    )
    (comp (ref "U4")
      (value "TPS54331DR")
      (footprint "easyedapro:SOIC-8_L5.0-W4.0-P1.27-LS6.0-BL")
      (description "功能类型:降压型;输出类型:可调;工作电压:3.5V~28V;输出电压:-;输出电流:3A;")
      (fields (field (name "Manufacturer") "TI(德州仪器)"))
      (libsource (lib "easyedapro") (part "TPS54331DR"))
    )
    (comp (ref "U5")
      (value "DRV8412DDWR")
      (footprint "easyedapro:HTSSOP-44_L14.0-W6.1-P0.64-LS8.1-BL-EP")
      (description "DRV8412 70V、6A 双通道 H 桥电机驱动器")
      (fields (field (name "Manufacturer") "TI(德州仪器)"))
      (libsource (lib "easyedapro") (part "DRV8412DDWR"))
    )
    (comp (ref "U7")
      (value "SN74AHC1G08DBVR")
      (footprint "easyedapro:SOT-23-5_L3.0-W1.7-P0.95-LS2.8-BR")
      (description "逻辑类型:与门;通道数:1;工作电压:2V~5.5V;静态电流(Iq):1uA;传播延迟(tpd):7.9ns@5V,50pF;")
      (fields (field (name "Manufacturer") "TI(德州仪器)"))
      (libsource (lib "easyedapro") (part "SN74AHC1G08DBVRG4"))
    )
    (comp (ref "U8")
      (value "DRV8412DDWR")
      (footprint "easyedapro:HTSSOP-44_L14.0-W6.1-P0.64-LS8.1-BL-EP")
      (description "DRV8412 70V、6A 双通道 H 桥电机驱动器")
      (fields (field (name "Manufacturer") "TI(德州仪器)"))
      (libsource (lib "easyedapro") (part "DRV8412DDWR"))
    )
    (comp (ref "U9")
      (value "SN74AHC1G08DBVR")
      (footprint "easyedapro:SOT-23-5_L3.0-W1.7-P0.95-LS2.8-BR")
      (description "逻辑类型:与门;通道数:1;工作电压:2V~5.5V;静态电流(Iq):1uA;传播延迟(tpd):7.9ns@5V,50pF;")
      (fields (field (name "Manufacturer") "TI(德州仪器)"))
      (libsource (lib "easyedapro") (part "SN74AHC1G08DBVRG4"))
    )
  )
  (nets
    (net (code "1") (name "+12V") (class "Default")
      (node (ref "C19") (pin "2") (pinfunction "2_2") (pintype "unspecified"))
      (node (ref "C20") (pin "2") (pinfunction "2_2") (pintype "unspecified"))
      (node (ref "C21") (pin "1") (pinfunction "1_1") (pintype "input"))
      (node (ref "C24") (pin "1") (pinfunction "1_1") (pintype "unspecified"))
      (node (ref "C25") (pin "1") (pinfunction "1_1") (pintype "unspecified"))
      (node (ref "C30") (pin "2") (pinfunction "2_2") (pintype "unspecified"))
      (node (ref "C31") (pin "1") (pinfunction "1_1") (pintype "unspecified"))
      (node (ref "C35") (pin "1") (pinfunction "1_1") (pintype "input"))
      (node (ref "C36") (pin "1") (pinfunction "1_1") (pintype "input"))
      (node (ref "C47") (pin "1") (pinfunction "1_1") (pintype "unspecified"))
      (node (ref "C48") (pin "1") (pinfunction "1_1") (pintype "unspecified"))
      (node (ref "C49") (pin "1") (pinfunction "1_1") (pintype "unspecified"))
      (node (ref "C53") (pin "2") (pinfunction "2_2") (pintype "unspecified"))
      (node (ref "C54") (pin "1") (pinfunction "1_1") (pintype "unspecified"))
      (node (ref "C63") (pin "1") (pinfunction "1_1") (pintype "unspecified"))
      (node (ref "L2") (pin "2") (pinfunction "2_2") (pintype "unspecified"))
      (node (ref "R11") (pin "2") (pinfunction "2_2") (pintype "unspecified"))
      (node (ref "U5") (pin "1") (pinfunction "GVDD_C_1") (pintype "unspecified"))
      (node (ref "U5") (pin "2") (pinfunction "VDD_2") (pintype "unspecified"))
      (node (ref "U5") (pin "22") (pinfunction "GVDD_B_22") (pintype "unspecified"))
      (node (ref "U5") (pin "23") (pinfunction "GVDD_A_23") (pintype "unspecified"))
      (node (ref "U5") (pin "44") (pinfunction "GVDD_D_44") (pintype "unspecified"))
      (node (ref "U8") (pin "1") (pinfunction "GVDD_C_1") (pintype "unspecified"))
      (node (ref "U8") (pin "2") (pinfunction "VDD_2") (pintype "unspecified"))
      (node (ref "U8") (pin "22") (pinfunction "GVDD_B_22") (pintype "unspecified"))
      (node (ref "U8") (pin "23") (pinfunction "GVDD_A_23") (pintype "unspecified"))
      (node (ref "U8") (pin "44") (pinfunction "GVDD_D_44") (pintype "unspecified"))
    )
    (net (code "2") (name "/+24V") (class "Default")
      (node (ref "CN1") (pin "1") (pinfunction "1_1") (pintype "unspecified"))
      (node (ref "D22") (pin "1") (pinfunction "-_1") (pintype "unspecified"))
      (node (ref "D24") (pin "1") (pinfunction "A_1") (pintype "unspecified"))
    )
    (net (code "3") (name "/C1_OUT_A") (class "Default")
      (node (ref "C46") (pin "1") (pinfunction "1_1") (pintype "unspecified"))
      (node (ref "L8") (pin "1") (pinfunction "1_1") (pintype "unspecified"))
      (node (ref "U5") (pin "28") (pinfunction "OUT_A_28") (pintype "unspecified"))
    )
    (net (code "4") (name "/C1_OUT_B") (class "Default")
      (node (ref "C41") (pin "1") (pinfunction "1_1") (pintype "unspecified"))
      (node (ref "L7") (pin "1") (pinfunction "1_1") (pintype "unspecified"))
      (node (ref "U5") (pin "31") (pinfunction "OUT_B_31") (pintype "unspecified"))
    )
    (net (code "5") (name "/C1_OUT_C") (class "Default")
      (node (ref "C40") (pin "1") (pinfunction "1_1") (pintype "unspecified"))
      (node (ref "L6") (pin "1") (pinfunction "1_1") (pintype "unspecified"))
      (node (ref "U5") (pin "36") (pinfunction "OUT_C_36") (pintype "unspecified"))
    )
    (net (code "6") (name "/C1_OUT_D") (class "Default")
      (node (ref "C32") (pin "1") (pinfunction "1_1") (pintype "unspecified"))
      (node (ref "L5") (pin "1") (pinfunction "1_1") (pintype "unspecified"))
      (node (ref "U5") (pin "39") (pinfunction "OUT_D_39") (pintype "unspecified"))
    )
    (net (code "7") (name "/C2_OUT_A") (class "Default")
      (node (ref "C62") (pin "1") (pinfunction "1_1") (pintype "unspecified"))
      (node (ref "L12") (pin "1") (pinfunction "1_1") (pintype "unspecified"))
      (node (ref "U8") (pin "28") (pinfunction "OUT_A_28") (pintype "unspecified"))
    )
    (net (code "8") (name "/C2_OUT_B") (class "Default")
      (node (ref "C57") (pin "1") (pinfunction "1_1") (pintype "unspecified"))
      (node (ref "L11") (pin "1") (pinfunction "1_1") (pintype "unspecified"))
      (node (ref "U8") (pin "31") (pinfunction "OUT_B_31") (pintype "unspecified"))
    )
    (net (code "9") (name "/C2_OUT_C") (class "Default")
      (node (ref "C56") (pin "1") (pinfunction "1_1") (pintype "unspecified"))
      (node (ref "L10") (pin "1") (pinfunction "1_1") (pintype "unspecified"))
      (node (ref "U8") (pin "36") (pinfunction "OUT_C_36") (pintype "unspecified"))
    )
    (net (code "10") (name "/C2_OUT_D") (class "Default")
      (node (ref "C55") (pin "1") (pinfunction "1_1") (pintype "unspecified"))
      (node (ref "L9") (pin "1") (pinfunction "1_1") (pintype "unspecified"))
      (node (ref "U8") (pin "39") (pinfunction "OUT_D_39") (pintype "unspecified"))
    )
    (net (code "11") (name "/M1_L") (class "Default")
      (node (ref "L8") (pin "2") (pinfunction "2_2") (pintype "unspecified"))
      (node (ref "P1") (pin "1") (pinfunction "1_1") (pintype "input"))
    )
    (net (code "12") (name "/M1_R") (class "Default")
      (node (ref "L7") (pin "2") (pinfunction "2_2") (pintype "unspecified"))
      (node (ref "P1") (pin "2") (pinfunction "2_2") (pintype "input"))
    )
    (net (code "13") (name "/M2_L") (class "Default")
      (node (ref "L6") (pin "2") (pinfunction "2_2") (pintype "unspecified"))
      (node (ref "P2") (pin "1") (pinfunction "1_1") (pintype "input"))
    )
    (net (code "14") (name "/M2_R") (class "Default")
      (node (ref "L5") (pin "2") (pinfunction "2_2") (pintype "unspecified"))
      (node (ref "P2") (pin "2") (pinfunction "2_2") (pintype "input"))
    )
    (net (code "15") (name "/M3_L") (class "Default")
      (node (ref "L12") (pin "2") (pinfunction "2_2") (pintype "unspecified"))
      (node (ref "P3") (pin "1") (pinfunction "1_1") (pintype "input"))
    )
    (net (code "16") (name "/M3_R") (class "Default")
      (node (ref "L11") (pin "2") (pinfunction "2_2") (pintype "unspecified"))
      (node (ref "P3") (pin "2") (pinfunction "2_2") (pintype "input"))
    )
    (net (code "17") (name "/M4_L") (class "Default")
      (node (ref "H2") (pin "1") (pinfunction "1_1") (pintype "unspecified"))
      (node (ref "L10") (pin "2") (pinfunction "2_2") (pintype "unspecified"))
    )
    (net (code "18") (name "/M4_R") (class "Default")
      (node (ref "H2") (pin "2") (pinfunction "2_2") (pintype "unspecified"))
      (node (ref "L9") (pin "2") (pinfunction "2_2") (pintype "unspecified"))
    )
    (net (code "19") (name "/PWM_M1_L") (class "Default")
      (node (ref "CN3") (pin "2") (pinfunction "2_2") (pintype "unspecified"))
      (node (ref "D16") (pin "1") (pinfunction "K_1") (pintype "unspecified"))
      (node (ref "R23") (pin "2") (pinfunction "2_2") (pintype "unspecified"))
    )
    (net (code "20") (name "/PWM_M1_R") (class "Default")
      (node (ref "CN3") (pin "1") (pinfunction "1_1") (pintype "unspecified"))
      (node (ref "D25") (pin "2") (pinfunction "A_2") (pintype "unspecified"))
      (node (ref "R22") (pin "2") (pinfunction "2_2") (pintype "unspecified"))
    )
    (net (code "21") (name "/PWM_M2_L") (class "Default")
      (node (ref "CN4") (pin "2") (pinfunction "2_2") (pintype "unspecified"))
      (node (ref "D27") (pin "2") (pinfunction "A_2") (pintype "unspecified"))
      (node (ref "R21") (pin "2") (pinfunction "2_2") (pintype "unspecified"))
    )
    (net (code "22") (name "/PWM_M2_R") (class "Default")
      (node (ref "CN4") (pin "1") (pinfunction "1_1") (pintype "unspecified"))
      (node (ref "D26") (pin "2") (pinfunction "A_2") (pintype "unspecified"))
      (node (ref "R20") (pin "2") (pinfunction "2_2") (pintype "unspecified"))
    )
    (net (code "23") (name "/PWM_M3_L") (class "Default")
      (node (ref "CN5") (pin "2") (pinfunction "2_2") (pintype "unspecified"))
      (node (ref "D29") (pin "2") (pinfunction "A_2") (pintype "unspecified"))
      (node (ref "R35") (pin "2") (pinfunction "2_2") (pintype "unspecified"))
    )
    (net (code "24") (name "/PWM_M3_R") (class "Default")
      (node (ref "CN5") (pin "1") (pinfunction "1_1") (pintype "unspecified"))
      (node (ref "D28") (pin "2") (pinfunction "A_2") (pintype "unspecified"))
      (node (ref "R34") (pin "2") (pinfunction "2_2") (pintype "unspecified"))
    )
    (net (code "25") (name "/PWM_M4_L") (class "Default")
      (node (ref "H1") (pin "1") (pinfunction "1_1") (pintype "unspecified"))
      (node (ref "R33") (pin "2") (pinfunction "2_2") (pintype "unspecified"))
    )
    (net (code "26") (name "/PWM_M4_R") (class "Default")
      (node (ref "H1") (pin "2") (pinfunction "2_2") (pintype "unspecified"))
      (node (ref "R32") (pin "2") (pinfunction "2_2") (pintype "unspecified"))
    )
    (net (code "27") (name "AGND_C1") (class "Default")
      (node (ref "C26") (pin "1") (pinfunction "1_1") (pintype "unspecified"))
      (node (ref "C27") (pin "1") (pinfunction "1_1") (pintype "unspecified"))
      (node (ref "R15") (pin "2") (pinfunction "2_2") (pintype "unspecified"))
      (node (ref "U5") (pin "12") (pinfunction "AGND_12") (pintype "unspecified"))
    )
    (net (code "28") (name "AGND_C2") (class "Default")
      (node (ref "C50") (pin "1") (pinfunction "1_1") (pintype "unspecified"))
      (node (ref "C51") (pin "1") (pinfunction "1_1") (pintype "unspecified"))
      (node (ref "R27") (pin "2") (pinfunction "2_2") (pintype "unspecified"))
      (node (ref "U8") (pin "12") (pinfunction "AGND_12") (pintype "unspecified"))
    )
    (net (code "29") (name "GND") (class "Default")
      (node (ref "C12") (pin "2") (pinfunction "2_2") (pintype "input"))
      (node (ref "C13") (pin "1") (pinfunction "1_1") (pintype "unspecified"))
      (node (ref "C14") (pin "1") (pinfunction "1_1") (pintype "unspecified"))
      (node (ref "C15") (pin "1") (pinfunction "1_1") (pintype "unspecified"))
      (node (ref "C18") (pin "1") (pinfunction "1_1") (pintype "unspecified"))
      (node (ref "C19") (pin "1") (pinfunction "1_1") (pintype "unspecified"))
      (node (ref "C20") (pin "1") (pinfunction "1_1") (pintype "unspecified"))
      (node (ref "C21") (pin "2") (pinfunction "2_2") (pintype "input"))
      (node (ref "C23") (pin "2") (pinfunction "2_2") (pintype "input"))
      (node (ref "C24") (pin "2") (pinfunction "2_2") (pintype "unspecified"))
      (node (ref "C25") (pin "2") (pinfunction "2_2") (pintype "unspecified"))
      (node (ref "C28") (pin "2") (pinfunction "2_2") (pintype "unspecified"))
      (node (ref "C30") (pin "1") (pinfunction "1_1") (pintype "unspecified"))
      (node (ref "C31") (pin "2") (pinfunction "2_2") (pintype "unspecified"))
      (node (ref "C33") (pin "1") (pinfunction "1_1") (pintype "unspecified"))
      (node (ref "C35") (pin "2") (pinfunction "2_2") (pintype "input"))
      (node (ref "C36") (pin "2") (pinfunction "2_2") (pintype "input"))
      (node (ref "C37") (pin "2") (pinfunction "2_2") (pintype "input"))
      (node (ref "C38") (pin "2") (pinfunction "2_2") (pintype "input"))
      (node (ref "C42") (pin "1") (pinfunction "1_1") (pintype "unspecified"))
      (node (ref "C43") (pin "1") (pinfunction "1_1") (pintype "unspecified"))
      (node (ref "C44") (pin "2") (pinfunction "2_2") (pintype "unspecified"))
      (node (ref "C45") (pin "2") (pinfunction "2_2") (pintype "unspecified"))
      (node (ref "C47") (pin "2") (pinfunction "2_2") (pintype "unspecified"))
      (node (ref "C48") (pin "2") (pinfunction "2_2") (pintype "unspecified"))
      (node (ref "C49") (pin "2") (pinfunction "2_2") (pintype "unspecified"))
      (node (ref "C52") (pin "2") (pinfunction "2_2") (pintype "unspecified"))
      (node (ref "C53") (pin "1") (pinfunction "1_1") (pintype "unspecified"))
      (node (ref "C54") (pin "2") (pinfunction "2_2") (pintype "unspecified"))
      (node (ref "C58") (pin "1") (pinfunction "1_1") (pintype "unspecified"))
      (node (ref "C59") (pin "1") (pinfunction "1_1") (pintype "unspecified"))
      (node (ref "C60") (pin "2") (pinfunction "2_2") (pintype "unspecified"))
      (node (ref "C61") (pin "2") (pinfunction "2_2") (pintype "unspecified"))
      (node (ref "C63") (pin "2") (pinfunction "2_2") (pintype "unspecified"))
      (node (ref "CN1") (pin "2") (pinfunction "2_2") (pintype "unspecified"))
      (node (ref "D16") (pin "2") (pinfunction "A_2") (pintype "unspecified"))
      (node (ref "D2") (pin "2") (pinfunction "A_2") (pintype "unspecified"))
      (node (ref "D22") (pin "2") (pinfunction "+_2") (pintype "unspecified"))
      (node (ref "D25") (pin "1") (pinfunction "K_1") (pintype "unspecified"))
      (node (ref "D26") (pin "1") (pinfunction "K_1") (pintype "unspecified"))
      (node (ref "D27") (pin "1") (pinfunction "K_1") (pintype "unspecified"))
      (node (ref "D28") (pin "1") (pinfunction "K_1") (pintype "unspecified"))
      (node (ref "D29") (pin "1") (pinfunction "K_1") (pintype "unspecified"))
      (node (ref "R10") (pin "1") (pinfunction "1_1") (pintype "unspecified"))
      (node (ref "R12") (pin "2") (pinfunction "2_2") (pintype "unspecified"))
      (node (ref "R13") (pin "2") (pinfunction "2_2") (pintype "unspecified"))
      (node (ref "R14") (pin "2") (pinfunction "2_2") (pintype "unspecified"))
      (node (ref "R19") (pin "1") (pinfunction "1_1") (pintype "unspecified"))
      (node (ref "R24") (pin "2") (pinfunction "2_2") (pintype "unspecified"))
      (node (ref "R25") (pin "2") (pinfunction "2_2") (pintype "unspecified"))
      (node (ref "R26") (pin "2") (pinfunction "2_2") (pintype "unspecified"))
      (node (ref "R31") (pin "1") (pinfunction "1_1") (pintype "unspecified"))
      (node (ref "R8") (pin "1") (pinfunction "1_1") (pintype "unspecified"))
      (node (ref "R9") (pin "1") (pinfunction "1_1") (pintype "unspecified"))
      (node (ref "U4") (pin "7") (pinfunction "GND_7") (pintype "unspecified"))
      (node (ref "U5") (pin "13") (pinfunction "GND_13") (pintype "unspecified"))
      (node (ref "U5") (pin "29") (pinfunction "GND_A_29") (pintype "unspecified"))
      (node (ref "U5") (pin "30") (pinfunction "GND_B_30") (pintype "unspecified"))
      (node (ref "U5") (pin "37") (pinfunction "GND_C_37") (pintype "unspecified"))
      (node (ref "U5") (pin "38") (pinfunction "GND_D_38") (pintype "unspecified"))
      (node (ref "U5") (pin "45") (pinfunction "PAD_45") (pintype "unspecified"))
      (node (ref "U7") (pin "3") (pinfunction "GND_3") (pintype "unspecified"))
      (node (ref "U8") (pin "13") (pinfunction "GND_13") (pintype "unspecified"))
      (node (ref "U8") (pin "29") (pinfunction "GND_A_29") (pintype "unspecified"))
      (node (ref "U8") (pin "30") (pinfunction "GND_B_30") (pintype "unspecified"))
      (node (ref "U8") (pin "37") (pinfunction "GND_C_37") (pintype "unspecified"))
      (node (ref "U8") (pin "38") (pinfunction "GND_D_38") (pintype "unspecified"))
      (node (ref "U8") (pin "45") (pinfunction "PAD_45") (pintype "unspecified"))
      (node (ref "U9") (pin "3") (pinfunction "GND_3") (pintype "unspecified"))
    )
    (net (code "30") (name "Net-(C16-Pad1)") (class "Default")
      (node (ref "C16") (pin "1") (pinfunction "1_1") (pintype "unspecified"))
      (node (ref "R9") (pin "2") (pinfunction "2_2") (pintype "unspecified"))
    )
    (net (code "31") (name "Net-(D2-C)") (class "Default")
      (node (ref "C17") (pin "2") (pinfunction "2_2") (pintype "unspecified"))
      (node (ref "D2") (pin "1") (pinfunction "C_1") (pintype "unspecified"))
      (node (ref "L2") (pin "1") (pinfunction "1_1") (pintype "unspecified"))
      (node (ref "U4") (pin "8") (pinfunction "PH_8") (pintype "unspecified"))
    )
    (net (code "32") (name "Net-(D24-K)") (class "Default")
      (node (ref "C23") (pin "1") (pinfunction "1_1") (pintype "input"))
      (node (ref "C33") (pin "2") (pinfunction "2_2") (pintype "unspecified"))
      (node (ref "D24") (pin "2") (pinfunction "K_2") (pintype "unspecified"))
      (node (ref "L4") (pin "1") (pinfunction "1_1") (pintype "unspecified"))
    )
    (net (code "33") (name "Net-(LED1-A)") (class "Default")
      (node (ref "LED1") (pin "2") (pinfunction "A_2") (pintype "unspecified"))
      (node (ref "Q1") (pin "3") (pinfunction "D_3") (pintype "unspecified"))
    )
    (net (code "34") (name "Net-(LED1-K)") (class "Default")
      (node (ref "LED1") (pin "1") (pinfunction "K_1") (pintype "unspecified"))
      (node (ref "R19") (pin "2") (pinfunction "2_2") (pintype "unspecified"))
    )
    (net (code "35") (name "Net-(LED2-A)") (class "Default")
      (node (ref "LED2") (pin "2") (pinfunction "A_2") (pintype "unspecified"))
      (node (ref "Q2") (pin "3") (pinfunction "D_3") (pintype "unspecified"))
    )
    (net (code "36") (name "Net-(LED2-K)") (class "Default")
      (node (ref "LED2") (pin "1") (pinfunction "K_1") (pintype "unspecified"))
      (node (ref "R31") (pin "2") (pinfunction "2_2") (pintype "unspecified"))
    )
    (net (code "37") (name "Net-(Q1-G)") (class "Default")
      (node (ref "Q1") (pin "1") (pinfunction "G_1") (pintype "unspecified"))
      (node (ref "R18") (pin "1") (pinfunction "1_1") (pintype "unspecified"))
      (node (ref "U7") (pin "4") (pinfunction "Y_4") (pintype "unspecified"))
    )
    (net (code "38") (name "Net-(Q1-S)") (class "Default")
      (node (ref "C28") (pin "1") (pinfunction "1_1") (pintype "unspecified"))
      (node (ref "Q1") (pin "2") (pinfunction "S_2") (pintype "unspecified"))
    )
    (net (code "39") (name "Net-(Q2-G)") (class "Default")
      (node (ref "Q2") (pin "1") (pinfunction "G_1") (pintype "unspecified"))
      (node (ref "R30") (pin "1") (pinfunction "1_1") (pintype "unspecified"))
      (node (ref "U9") (pin "4") (pinfunction "Y_4") (pintype "unspecified"))
    )
    (net (code "40") (name "Net-(Q2-S)") (class "Default")
      (node (ref "C52") (pin "1") (pinfunction "1_1") (pintype "unspecified"))
      (node (ref "Q2") (pin "2") (pinfunction "S_2") (pintype "unspecified"))
    )
    (net (code "41") (name "Net-(U4-BOOT)") (class "Default")
      (node (ref "C17") (pin "1") (pinfunction "1_1") (pintype "unspecified"))
      (node (ref "U4") (pin "1") (pinfunction "BOOT_1") (pintype "unspecified"))
    )
    (net (code "42") (name "Net-(U4-COMP)") (class "Default")
      (node (ref "C16") (pin "2") (pinfunction "2_2") (pintype "unspecified"))
      (node (ref "C18") (pin "2") (pinfunction "2_2") (pintype "unspecified"))
      (node (ref "U4") (pin "6") (pinfunction "COMP_6") (pintype "unspecified"))
    )
    (net (code "43") (name "Net-(U4-EN)") (class "Default")
      (node (ref "R7") (pin "1") (pinfunction "1_1") (pintype "unspecified"))
      (node (ref "R8") (pin "2") (pinfunction "2_2") (pintype "unspecified"))
      (node (ref "U4") (pin "3") (pinfunction "EN_3") (pintype "unspecified"))
    )
    (net (code "44") (name "Net-(U4-SS)") (class "Default")
      (node (ref "C15") (pin "2") (pinfunction "2_2") (pintype "unspecified"))
      (node (ref "U4") (pin "4") (pinfunction "SS_4") (pintype "unspecified"))
    )
    (net (code "45") (name "Net-(U4-VSENSE)") (class "Default")
      (node (ref "R10") (pin "2") (pinfunction "2_2") (pintype "unspecified"))
      (node (ref "R11") (pin "1") (pinfunction "1_1") (pintype "unspecified"))
      (node (ref "U4") (pin "5") (pinfunction "VSENSE_5") (pintype "unspecified"))
    )
    (net (code "46") (name "Net-(U5-BST_A)") (class "Default")
      (node (ref "C46") (pin "2") (pinfunction "2_2") (pintype "unspecified"))
      (node (ref "U5") (pin "24") (pinfunction "BST_A_24") (pintype "unspecified"))
    )
    (net (code "47") (name "Net-(U5-BST_B)") (class "Default")
      (node (ref "C41") (pin "2") (pinfunction "2_2") (pintype "unspecified"))
      (node (ref "U5") (pin "33") (pinfunction "BST_B_33") (pintype "unspecified"))
    )
    (net (code "48") (name "Net-(U5-BST_C)") (class "Default")
      (node (ref "C40") (pin "2") (pinfunction "2_2") (pintype "unspecified"))
      (node (ref "U5") (pin "34") (pinfunction "BST_C_34") (pintype "unspecified"))
    )
    (net (code "49") (name "Net-(U5-BST_D)") (class "Default")
      (node (ref "C32") (pin "2") (pinfunction "2_2") (pintype "unspecified"))
      (node (ref "U5") (pin "43") (pinfunction "BST_D_43") (pintype "unspecified"))
    )
    (net (code "50") (name "Net-(U5-FAULT#)") (class "Default")
      (node (ref "R16") (pin "1") (pinfunction "1_1") (pintype "unspecified"))
      (node (ref "U5") (pin "18") (pinfunction "FAULT#_18") (pintype "unspecified"))
      (node (ref "U7") (pin "2") (pinfunction "B_2") (pintype "unspecified"))
    )
    (net (code "51") (name "Net-(U5-M1)") (class "Default")
      (node (ref "R12") (pin "1") (pinfunction "1_1") (pintype "unspecified"))
      (node (ref "U5") (pin "8") (pinfunction "M1_8") (pintype "unspecified"))
    )
    (net (code "52") (name "Net-(U5-M2)") (class "Default")
      (node (ref "R13") (pin "1") (pinfunction "1_1") (pintype "unspecified"))
      (node (ref "U5") (pin "9") (pinfunction "M2_9") (pintype "unspecified"))
    )
    (net (code "53") (name "Net-(U5-M3)") (class "Default")
      (node (ref "R14") (pin "1") (pinfunction "1_1") (pintype "unspecified"))
      (node (ref "U5") (pin "10") (pinfunction "M3_10") (pintype "unspecified"))
    )
    (net (code "54") (name "Net-(U5-OC_ADJ)") (class "Default")
      (node (ref "R15") (pin "1") (pinfunction "1_1") (pintype "unspecified"))
      (node (ref "U5") (pin "14") (pinfunction "OC_ADJ_14") (pintype "unspecified"))
    )
    (net (code "55") (name "Net-(U5-OTW#)") (class "Default")
      (node (ref "R17") (pin "1") (pinfunction "1_1") (pintype "unspecified"))
      (node (ref "U5") (pin "21") (pinfunction "OTW#_21") (pintype "unspecified"))
      (node (ref "U7") (pin "1") (pinfunction "A_1") (pintype "unspecified"))
    )
    (net (code "56") (name "Net-(U5-PWM_A)") (class "Default")
      (node (ref "R23") (pin "1") (pinfunction "1_1") (pintype "unspecified"))
      (node (ref "U5") (pin "17") (pinfunction "PWM_A_17") (pintype "unspecified"))
    )
    (net (code "57") (name "Net-(U5-PWM_B)") (class "Default")
      (node (ref "R22") (pin "1") (pinfunction "1_1") (pintype "unspecified"))
      (node (ref "U5") (pin "15") (pinfunction "PWM_B_15") (pintype "unspecified"))
    )
    (net (code "58") (name "Net-(U5-PWM_C)") (class "Default")
      (node (ref "R21") (pin "1") (pinfunction "1_1") (pintype "unspecified"))
      (node (ref "U5") (pin "7") (pinfunction "PWM_C_7") (pintype "unspecified"))
    )
    (net (code "59") (name "Net-(U5-PWM_D)") (class "Default")
      (node (ref "R20") (pin "1") (pinfunction "1_1") (pintype "unspecified"))
      (node (ref "U5") (pin "5") (pinfunction "PWM_D_5") (pintype "unspecified"))
    )
    (net (code "60") (name "Net-(U8-BST_A)") (class "Default")
      (node (ref "C62") (pin "2") (pinfunction "2_2") (pintype "unspecified"))
      (node (ref "U8") (pin "24") (pinfunction "BST_A_24") (pintype "unspecified"))
    )
    (net (code "61") (name "Net-(U8-BST_B)") (class "Default")
      (node (ref "C57") (pin "2") (pinfunction "2_2") (pintype "unspecified"))
      (node (ref "U8") (pin "33") (pinfunction "BST_B_33") (pintype "unspecified"))
    )
    (net (code "62") (name "Net-(U8-BST_C)") (class "Default")
      (node (ref "C56") (pin "2") (pinfunction "2_2") (pintype "unspecified"))
      (node (ref "U8") (pin "34") (pinfunction "BST_C_34") (pintype "unspecified"))
    )
    (net (code "63") (name "Net-(U8-BST_D)") (class "Default")
      (node (ref "C55") (pin "2") (pinfunction "2_2") (pintype "unspecified"))
      (node (ref "U8") (pin "43") (pinfunction "BST_D_43") (pintype "unspecified"))
    )
    (net (code "64") (name "Net-(U8-FAULT#)") (class "Default")
      (node (ref "R28") (pin "1") (pinfunction "1_1") (pintype "unspecified"))
      (node (ref "U8") (pin "18") (pinfunction "FAULT#_18") (pintype "unspecified"))
      (node (ref "U9") (pin "2") (pinfunction "B_2") (pintype "unspecified"))
    )
    (net (code "65") (name "Net-(U8-M1)") (class "Default")
      (node (ref "R24") (pin "1") (pinfunction "1_1") (pintype "unspecified"))
      (node (ref "U8") (pin "8") (pinfunction "M1_8") (pintype "unspecified"))
    )
    (net (code "66") (name "Net-(U8-M2)") (class "Default")
      (node (ref "R25") (pin "1") (pinfunction "1_1") (pintype "unspecified"))
      (node (ref "U8") (pin "9") (pinfunction "M2_9") (pintype "unspecified"))
    )
    (net (code "67") (name "Net-(U8-M3)") (class "Default")
      (node (ref "R26") (pin "1") (pinfunction "1_1") (pintype "unspecified"))
      (node (ref "U8") (pin "10") (pinfunction "M3_10") (pintype "unspecified"))
    )
    (net (code "68") (name "Net-(U8-OC_ADJ)") (class "Default")
      (node (ref "R27") (pin "1") (pinfunction "1_1") (pintype "unspecified"))
      (node (ref "U8") (pin "14") (pinfunction "OC_ADJ_14") (pintype "unspecified"))
    )
    (net (code "69") (name "Net-(U8-OTW#)") (class "Default")
      (node (ref "R29") (pin "1") (pinfunction "1_1") (pintype "unspecified"))
      (node (ref "U8") (pin "21") (pinfunction "OTW#_21") (pintype "unspecified"))
      (node (ref "U9") (pin "1") (pinfunction "A_1") (pintype "unspecified"))
    )
    (net (code "70") (name "Net-(U8-PWM_A)") (class "Default")
      (node (ref "R35") (pin "1") (pinfunction "1_1") (pintype "unspecified"))
      (node (ref "U8") (pin "17") (pinfunction "PWM_A_17") (pintype "unspecified"))
    )
    (net (code "71") (name "Net-(U8-PWM_B)") (class "Default")
      (node (ref "R34") (pin "1") (pinfunction "1_1") (pintype "unspecified"))
      (node (ref "U8") (pin "15") (pinfunction "PWM_B_15") (pintype "unspecified"))
    )
    (net (code "72") (name "Net-(U8-PWM_C)") (class "Default")
      (node (ref "R33") (pin "1") (pinfunction "1_1") (pintype "unspecified"))
      (node (ref "U8") (pin "7") (pinfunction "PWM_C_7") (pintype "unspecified"))
    )
    (net (code "73") (name "Net-(U8-PWM_D)") (class "Default")
      (node (ref "R32") (pin "1") (pinfunction "1_1") (pintype "unspecified"))
      (node (ref "U8") (pin "5") (pinfunction "PWM_D_5") (pintype "unspecified"))
    )
    (net (code "74") (name "VCC_24V") (class "Default")
      (node (ref "C12") (pin "1") (pinfunction "1_1") (pintype "input"))
      (node (ref "C13") (pin "2") (pinfunction "2_2") (pintype "unspecified"))
      (node (ref "C14") (pin "2") (pinfunction "2_2") (pintype "unspecified"))
      (node (ref "C37") (pin "1") (pinfunction "1_1") (pintype "input"))
      (node (ref "C38") (pin "1") (pinfunction "1_1") (pintype "input"))
      (node (ref "C42") (pin "2") (pinfunction "2_2") (pintype "unspecified"))
      (node (ref "C43") (pin "2") (pinfunction "2_2") (pintype "unspecified"))
      (node (ref "C44") (pin "1") (pinfunction "1_1") (pintype "unspecified"))
      (node (ref "C45") (pin "1") (pinfunction "1_1") (pintype "unspecified"))
      (node (ref "C58") (pin "2") (pinfunction "2_2") (pintype "unspecified"))
      (node (ref "C59") (pin "2") (pinfunction "2_2") (pintype "unspecified"))
      (node (ref "C60") (pin "1") (pinfunction "1_1") (pintype "unspecified"))
      (node (ref "C61") (pin "1") (pinfunction "1_1") (pintype "unspecified"))
      (node (ref "L4") (pin "2") (pinfunction "2_2") (pintype "unspecified"))
      (node (ref "R7") (pin "2") (pinfunction "2_2") (pintype "unspecified"))
      (node (ref "U4") (pin "2") (pinfunction "VIN_2") (pintype "unspecified"))
      (node (ref "U5") (pin "26") (pinfunction "PVDD_A_26") (pintype "unspecified"))
      (node (ref "U5") (pin "27") (pinfunction "PVDD_A_27") (pintype "unspecified"))
      (node (ref "U5") (pin "32") (pinfunction "PVDD_B_32") (pintype "unspecified"))
      (node (ref "U5") (pin "35") (pinfunction "PVDD_C_35") (pintype "unspecified"))
      (node (ref "U5") (pin "40") (pinfunction "PVDD_D_40") (pintype "unspecified"))
      (node (ref "U5") (pin "41") (pinfunction "PVDD_D_41") (pintype "unspecified"))
      (node (ref "U8") (pin "26") (pinfunction "PVDD_A_26") (pintype "unspecified"))
      (node (ref "U8") (pin "27") (pinfunction "PVDD_A_27") (pintype "unspecified"))
      (node (ref "U8") (pin "32") (pinfunction "PVDD_B_32") (pintype "unspecified"))
      (node (ref "U8") (pin "35") (pinfunction "PVDD_C_35") (pintype "unspecified"))
      (node (ref "U8") (pin "40") (pinfunction "PVDD_D_40") (pintype "unspecified"))
      (node (ref "U8") (pin "41") (pinfunction "PVDD_D_41") (pintype "unspecified"))
    )
    (net (code "75") (name "VREF_C1") (class "Default")
      (node (ref "C26") (pin "2") (pinfunction "2_2") (pintype "unspecified"))
      (node (ref "C27") (pin "2") (pinfunction "2_2") (pintype "unspecified"))
      (node (ref "R16") (pin "2") (pinfunction "2_2") (pintype "unspecified"))
      (node (ref "R17") (pin "2") (pinfunction "2_2") (pintype "unspecified"))
      (node (ref "R18") (pin "2") (pinfunction "2_2") (pintype "unspecified"))
      (node (ref "U5") (pin "11") (pinfunction "VREG_11") (pintype "unspecified"))
      (node (ref "U5") (pin "16") (pinfunction "RESET_AB#_16") (pintype "unspecified"))
      (node (ref "U5") (pin "6") (pinfunction "RESET_CD#_6") (pintype "unspecified"))
      (node (ref "U7") (pin "5") (pinfunction "VCC_5") (pintype "unspecified"))
    )
    (net (code "76") (name "VREF_C2") (class "Default")
      (node (ref "C50") (pin "2") (pinfunction "2_2") (pintype "unspecified"))
      (node (ref "C51") (pin "2") (pinfunction "2_2") (pintype "unspecified"))
      (node (ref "R28") (pin "2") (pinfunction "2_2") (pintype "unspecified"))
      (node (ref "R29") (pin "2") (pinfunction "2_2") (pintype "unspecified"))
      (node (ref "R30") (pin "2") (pinfunction "2_2") (pintype "unspecified"))
      (node (ref "U8") (pin "11") (pinfunction "VREG_11") (pintype "unspecified"))
      (node (ref "U8") (pin "16") (pinfunction "RESET_AB#_16") (pintype "unspecified"))
      (node (ref "U8") (pin "6") (pinfunction "RESET_CD#_6") (pintype "unspecified"))
      (node (ref "U9") (pin "5") (pinfunction "VCC_5") (pintype "unspecified"))
    )
    (net (code "77") (name "unconnected-(SCREW1-Pad1)") (class "Default")
      (node (ref "SCREW1") (pin "1") (pinfunction "1_1") (pintype "input"))
    )
    (net (code "78") (name "unconnected-(SCREW2-Pad1)") (class "Default")
      (node (ref "SCREW2") (pin "1") (pinfunction "1_1") (pintype "input"))
    )
    (net (code "79") (name "unconnected-(SCREW3-Pad1)") (class "Default")
      (node (ref "SCREW3") (pin "1") (pinfunction "1_1") (pintype "input"))
    )
    (net (code "80") (name "unconnected-(SCREW4-Pad1)") (class "Default")
      (node (ref "SCREW4") (pin "1") (pinfunction "1_1") (pintype "input"))
    )
    (net (code "81") (name "unconnected-(U5-NC-Pad3)") (class "Default")
      (node (ref "U5") (pin "3") (pinfunction "NC_3") (pintype "unspecified+no_connect"))
    )
    (net (code "82") (name "unconnected-(U5-NC-Pad4)") (class "Default")
      (node (ref "U5") (pin "4") (pinfunction "NC_4") (pintype "unspecified+no_connect"))
    )
    (net (code "83") (name "unconnected-(U5-NC-Pad19)") (class "Default")
      (node (ref "U5") (pin "19") (pinfunction "NC_19") (pintype "unspecified+no_connect"))
    )
    (net (code "84") (name "unconnected-(U5-NC-Pad20)") (class "Default")
      (node (ref "U5") (pin "20") (pinfunction "NC_20") (pintype "unspecified+no_connect"))
    )
    (net (code "85") (name "unconnected-(U5-NC-Pad25)") (class "Default")
      (node (ref "U5") (pin "25") (pinfunction "NC_25") (pintype "unspecified+no_connect"))
    )
    (net (code "86") (name "unconnected-(U5-NC-Pad42)") (class "Default")
      (node (ref "U5") (pin "42") (pinfunction "NC_42") (pintype "unspecified+no_connect"))
    )
    (net (code "87") (name "unconnected-(U8-NC-Pad3)") (class "Default")
      (node (ref "U8") (pin "3") (pinfunction "NC_3") (pintype "unspecified+no_connect"))
    )
    (net (code "88") (name "unconnected-(U8-NC-Pad4)") (class "Default")
      (node (ref "U8") (pin "4") (pinfunction "NC_4") (pintype "unspecified+no_connect"))
    )
    (net (code "89") (name "unconnected-(U8-NC-Pad19)") (class "Default")
      (node (ref "U8") (pin "19") (pinfunction "NC_19") (pintype "unspecified+no_connect"))
    )
    (net (code "90") (name "unconnected-(U8-NC-Pad20)") (class "Default")
      (node (ref "U8") (pin "20") (pinfunction "NC_20") (pintype "unspecified+no_connect"))
    )
    (net (code "91") (name "unconnected-(U8-NC-Pad25)") (class "Default")
      (node (ref "U8") (pin "25") (pinfunction "NC_25") (pintype "unspecified+no_connect"))
    )
    (net (code "92") (name "unconnected-(U8-NC-Pad42)") (class "Default")
      (node (ref "U8") (pin "42") (pinfunction "NC_42") (pintype "unspecified+no_connect"))
    )
  )
)
